# DCDC-12V5V5A.net
KiCad netlist of a schematic drawn in EAGLE
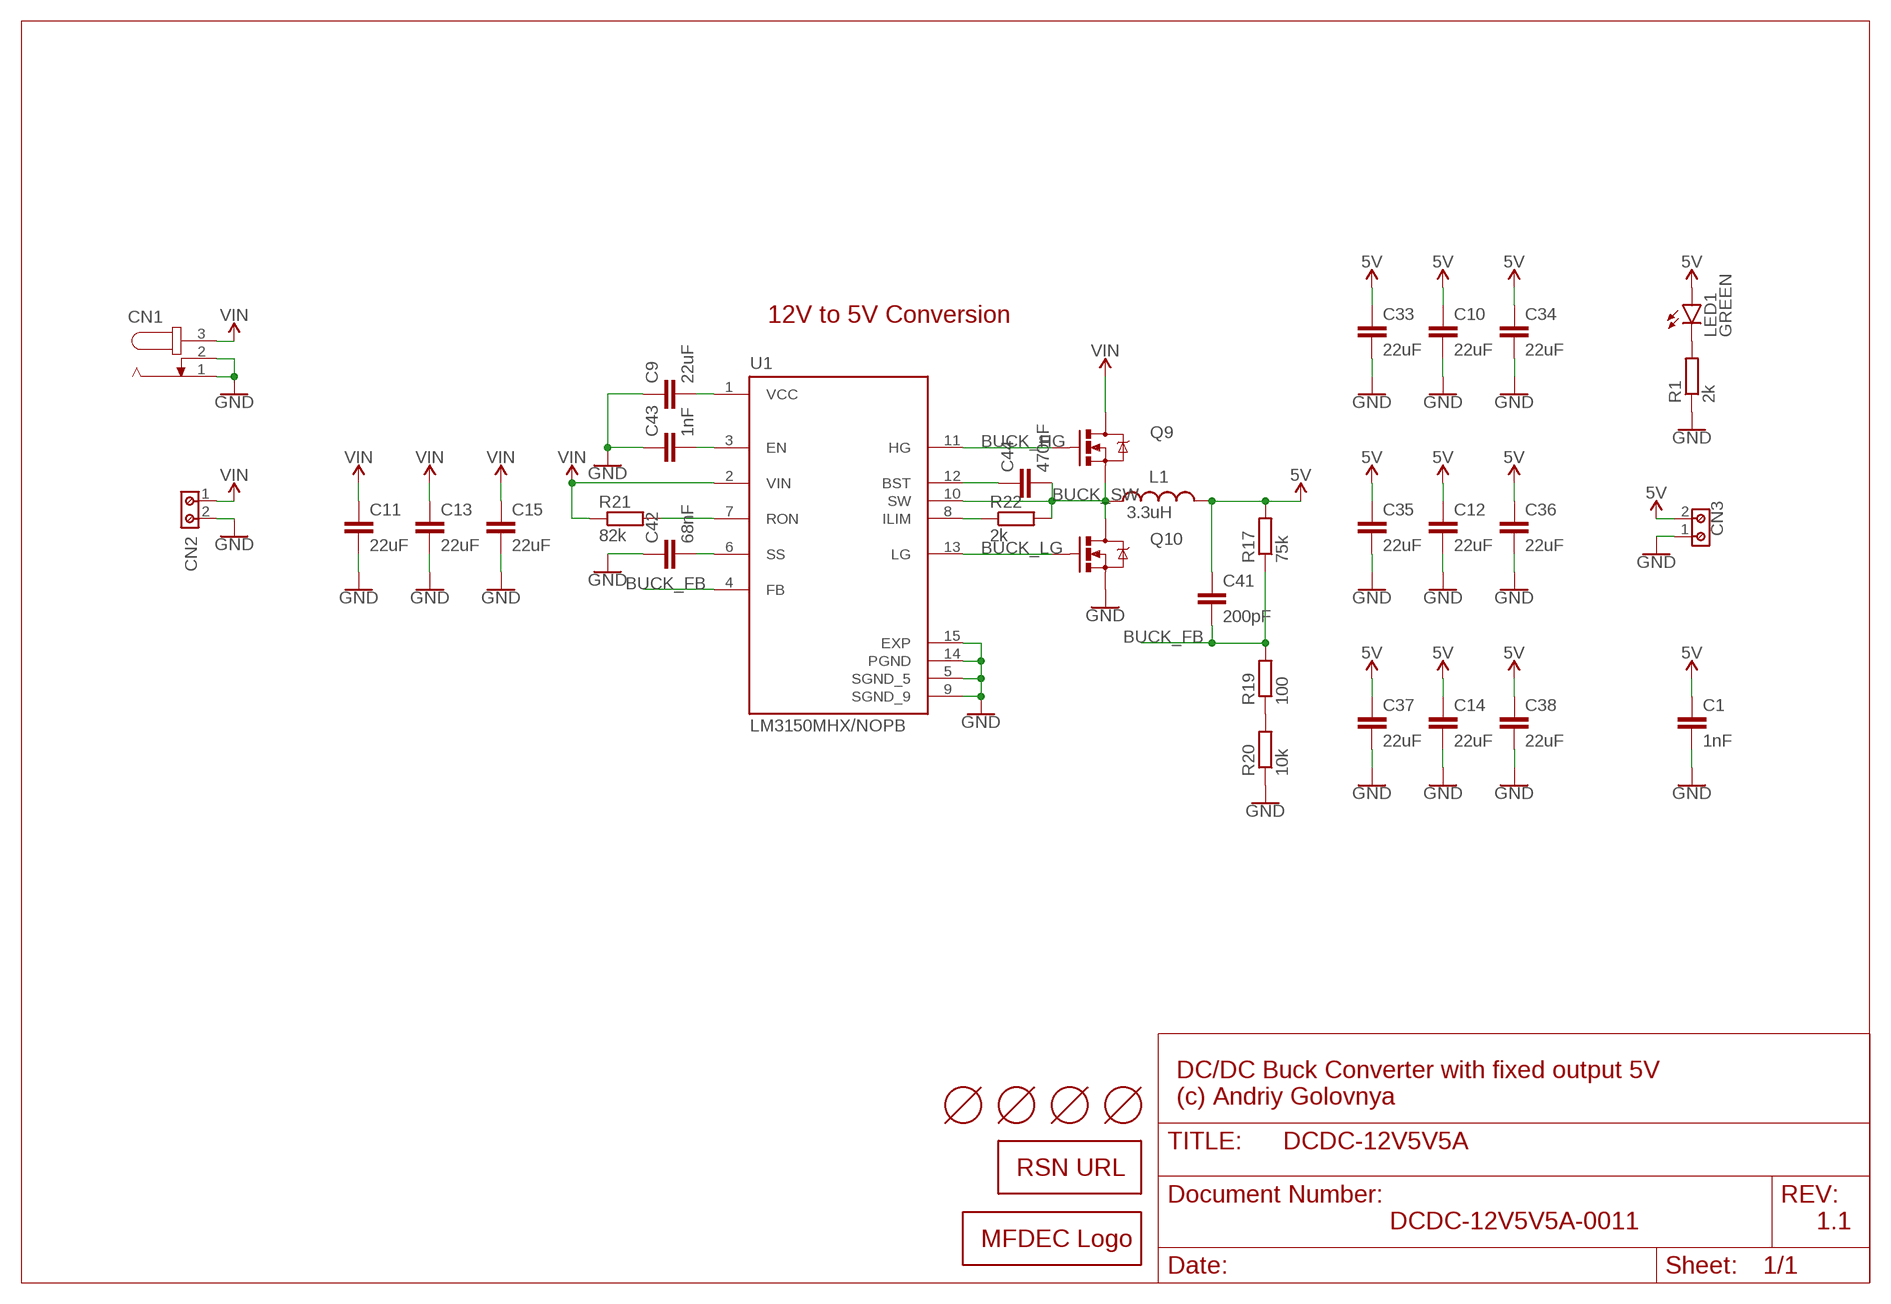
[diagram p0: schematic, sheet 1]

(export (version "E")
  (design (tool "Eeschema 10.0.6"))
  (components
    (comp (ref "C1")
      (value "1nF")
      (footprint "eagle-import:C0603K")
      (libsource (lib "eagle-import") (part "C-EUC0603K"))
    )
    (comp (ref "C9")
      (value "22uF")
      (footprint "eagle-import:C0805K")
      (libsource (lib "eagle-import") (part "C-EUC0805K"))
    )
    (comp (ref "C10")
      (value "22uF")
      (footprint "eagle-import:C0805K")
      (libsource (lib "eagle-import") (part "C-EUC0805K"))
    )
    (comp (ref "C11")
      (value "22uF")
      (footprint "eagle-import:C0805K")
      (libsource (lib "eagle-import") (part "C-EUC0805K"))
    )
    (comp (ref "C12")
      (value "22uF")
      (footprint "eagle-import:C0805K")
      (libsource (lib "eagle-import") (part "C-EUC0805K"))
    )
    (comp (ref "C13")
      (value "22uF")
      (footprint "eagle-import:C0805K")
      (libsource (lib "eagle-import") (part "C-EUC0805K"))
    )
    (comp (ref "C14")
      (value "22uF")
      (footprint "eagle-import:C0805K")
      (libsource (lib "eagle-import") (part "C-EUC0805K"))
    )
    (comp (ref "C15")
      (value "22uF")
      (footprint "eagle-import:C0805K")
      (libsource (lib "eagle-import") (part "C-EUC0805K"))
    )
    (comp (ref "C33")
      (value "22uF")
      (footprint "eagle-import:C0805K")
      (libsource (lib "eagle-import") (part "C-EUC0805K"))
    )
    (comp (ref "C34")
      (value "22uF")
      (footprint "eagle-import:C0805K")
      (libsource (lib "eagle-import") (part "C-EUC0805K"))
    )
    (comp (ref "C35")
      (value "22uF")
      (footprint "eagle-import:C0805K")
      (libsource (lib "eagle-import") (part "C-EUC0805K"))
    )
    (comp (ref "C36")
      (value "22uF")
      (footprint "eagle-import:C0805K")
      (libsource (lib "eagle-import") (part "C-EUC0805K"))
    )
    (comp (ref "C37")
      (value "22uF")
      (footprint "eagle-import:C0805K")
      (libsource (lib "eagle-import") (part "C-EUC0805K"))
    )
    (comp (ref "C38")
      (value "22uF")
      (footprint "eagle-import:C0805K")
      (libsource (lib "eagle-import") (part "C-EUC0805K"))
    )
    (comp (ref "C41")
      (value "200pF")
      (footprint "eagle-import:C0603K")
      (libsource (lib "eagle-import") (part "C-EUC0603K"))
    )
    (comp (ref "C42")
      (value "68nF")
      (footprint "eagle-import:C0603K")
      (libsource (lib "eagle-import") (part "C-EUC0603K"))
    )
    (comp (ref "C43")
      (value "1nF")
      (footprint "eagle-import:C0603K")
      (libsource (lib "eagle-import") (part "C-EUC0603K"))
    )
    (comp (ref "C44")
      (value "470nF")
      (footprint "eagle-import:C0603K")
      (libsource (lib "eagle-import") (part "C-EUC0603K"))
    )
    (comp (ref "CN1")
      (value "JACK-PLUG1")
      (footprint "eagle-import:SPC4078")
      (libsource (lib "eagle-import") (part "JACK-PLUG1"))
    )
    (comp (ref "CN2")
      (value "691213510002")
      (footprint "eagle-import:691213510002")
      (libsource (lib "eagle-import") (part "691213510002"))
    )
    (comp (ref "CN3")
      (value "691213510002")
      (footprint "eagle-import:691213510002")
      (libsource (lib "eagle-import") (part "691213510002"))
    )
    (comp (ref "HOLE1")
      (value "TOOLINGHOLE")
      (footprint "eagle-import:TOOLING-HOLE")
      (libsource (lib "eagle-import") (part "TOOLINGHOLE"))
    )
    (comp (ref "HOLE2")
      (value "TOOLINGHOLE")
      (footprint "eagle-import:TOOLING-HOLE")
      (libsource (lib "eagle-import") (part "TOOLINGHOLE"))
    )
    (comp (ref "HOLE3")
      (value "TOOLINGHOLE")
      (footprint "eagle-import:TOOLING-HOLE")
      (libsource (lib "eagle-import") (part "TOOLINGHOLE"))
    )
    (comp (ref "HOLE4")
      (value "TOOLINGHOLE")
      (footprint "eagle-import:TOOLING-HOLE")
      (libsource (lib "eagle-import") (part "TOOLINGHOLE"))
    )
    (comp (ref "L1")
      (value "3.3uH")
      (footprint "eagle-import:WE-CHSA_1011")
      (libsource (lib "eagle-import") (part "WE-CHSA_1011_7843330330"))
    )
    (comp (ref "LED1")
      (value "GREEN")
      (footprint "eagle-import:SML0603")
      (libsource (lib "eagle-import") (part "LEDSML0603"))
    )
    (comp (ref "LOGO1")
      (value "RSNURL_QR_8MM")
      (footprint "eagle-import:RSNURL_QR_8MM")
      (libsource (lib "eagle-import") (part "RSNURL_QR_8MM"))
    )
    (comp (ref "LOGO2")
      (value "MFDECLOGO_L_10MM")
      (footprint "eagle-import:MFDEC_L_10MM")
      (libsource (lib "eagle-import") (part "MFDECLOGO_L_10MM"))
    )
    (comp (ref "Q9")
      (value "NMOSFET")
      (footprint "eagle-import:DPAK")
      (libsource (lib "eagle-import") (part "MOSFET-NCHANNELFDD8780"))
    )
    (comp (ref "Q10")
      (value "NMOSFET")
      (footprint "eagle-import:DPAK")
      (libsource (lib "eagle-import") (part "MOSFET-NCHANNELFDD8780"))
    )
    (comp (ref "R1")
      (value "2k")
      (footprint "eagle-import:R0603")
      (libsource (lib "eagle-import") (part "R-EU_R0603"))
    )
    (comp (ref "R17")
      (value "75k")
      (footprint "eagle-import:R0603")
      (libsource (lib "eagle-import") (part "R-EU_R0603"))
    )
    (comp (ref "R19")
      (value "100")
      (footprint "eagle-import:R0603")
      (libsource (lib "eagle-import") (part "R-EU_R0603"))
    )
    (comp (ref "R20")
      (value "10k")
      (footprint "eagle-import:R0603")
      (libsource (lib "eagle-import") (part "R-EU_R0603"))
    )
    (comp (ref "R21")
      (value "82k")
      (footprint "eagle-import:R0603")
      (libsource (lib "eagle-import") (part "R-EU_R0603"))
    )
    (comp (ref "R22")
      (value "2k")
      (footprint "eagle-import:R0603")
      (libsource (lib "eagle-import") (part "R-EU_R0603"))
    )
    (comp (ref "U1")
      (value "LM3150MHX/NOPB")
      (footprint "eagle-import:SOP65P640X110-15N")
      (fields (field (name "MF") "Texas Instruments"))
      (libsource (lib "eagle-import") (part "LM3150MHX/NOPB"))
    )
  )
  (nets
    (net (code "1") (name "/BUCK_FB") (class "Default")
      (node (ref "C41") (pin "2") (pinfunction "2_2") (pintype "passive"))
      (node (ref "R17") (pin "1") (pinfunction "1_1") (pintype "passive"))
      (node (ref "R19") (pin "2") (pinfunction "2_2") (pintype "passive"))
      (node (ref "U1") (pin "4") (pinfunction "FB_4") (pintype "input"))
    )
    (net (code "2") (name "/BUCK_HG") (class "Default")
      (node (ref "Q9") (pin "1") (pinfunction "G_1") (pintype "passive"))
      (node (ref "U1") (pin "11") (pinfunction "HG_11") (pintype "output"))
    )
    (net (code "3") (name "/BUCK_LG") (class "Default")
      (node (ref "Q10") (pin "1") (pinfunction "G_1") (pintype "passive"))
      (node (ref "U1") (pin "13") (pinfunction "LG_13") (pintype "output"))
    )
    (net (code "4") (name "/BUCK_SW") (class "Default")
      (node (ref "C44") (pin "2") (pinfunction "2_2") (pintype "passive"))
      (node (ref "L1") (pin "1") (pinfunction "1_1") (pintype "passive"))
      (node (ref "Q10") (pin "4") (pinfunction "D_4") (pintype "passive"))
      (node (ref "Q9") (pin "3") (pinfunction "S_3") (pintype "passive"))
      (node (ref "R22") (pin "2") (pinfunction "2_2") (pintype "passive"))
      (node (ref "U1") (pin "10") (pinfunction "SW_10") (pintype "output"))
    )
    (net (code "5") (name "5V") (class "Default")
      (node (ref "C1") (pin "1") (pinfunction "1_1") (pintype "passive"))
      (node (ref "C10") (pin "1") (pinfunction "1_1") (pintype "passive"))
      (node (ref "C12") (pin "1") (pinfunction "1_1") (pintype "passive"))
      (node (ref "C14") (pin "1") (pinfunction "1_1") (pintype "passive"))
      (node (ref "C33") (pin "1") (pinfunction "1_1") (pintype "passive"))
      (node (ref "C34") (pin "1") (pinfunction "1_1") (pintype "passive"))
      (node (ref "C35") (pin "1") (pinfunction "1_1") (pintype "passive"))
      (node (ref "C36") (pin "1") (pinfunction "1_1") (pintype "passive"))
      (node (ref "C37") (pin "1") (pinfunction "1_1") (pintype "passive"))
      (node (ref "C38") (pin "1") (pinfunction "1_1") (pintype "passive"))
      (node (ref "C41") (pin "1") (pinfunction "1_1") (pintype "passive"))
      (node (ref "CN3") (pin "2") (pinfunction "2_2") (pintype "passive"))
      (node (ref "L1") (pin "2") (pinfunction "2_2") (pintype "passive"))
      (node (ref "LED1") (pin "A") (pinfunction "A_A") (pintype "passive"))
      (node (ref "R17") (pin "2") (pinfunction "2_2") (pintype "passive"))
    )
    (net (code "6") (name "GND") (class "Default")
      (node (ref "C1") (pin "2") (pinfunction "2_2") (pintype "passive"))
      (node (ref "C10") (pin "2") (pinfunction "2_2") (pintype "passive"))
      (node (ref "C11") (pin "2") (pinfunction "2_2") (pintype "passive"))
      (node (ref "C12") (pin "2") (pinfunction "2_2") (pintype "passive"))
      (node (ref "C13") (pin "2") (pinfunction "2_2") (pintype "passive"))
      (node (ref "C14") (pin "2") (pinfunction "2_2") (pintype "passive"))
      (node (ref "C15") (pin "2") (pinfunction "2_2") (pintype "passive"))
      (node (ref "C33") (pin "2") (pinfunction "2_2") (pintype "passive"))
      (node (ref "C34") (pin "2") (pinfunction "2_2") (pintype "passive"))
      (node (ref "C35") (pin "2") (pinfunction "2_2") (pintype "passive"))
      (node (ref "C36") (pin "2") (pinfunction "2_2") (pintype "passive"))
      (node (ref "C37") (pin "2") (pinfunction "2_2") (pintype "passive"))
      (node (ref "C38") (pin "2") (pinfunction "2_2") (pintype "passive"))
      (node (ref "C42") (pin "1") (pinfunction "1_1") (pintype "passive"))
      (node (ref "C43") (pin "1") (pinfunction "1_1") (pintype "passive"))
      (node (ref "C9") (pin "1") (pinfunction "1_1") (pintype "passive"))
      (node (ref "CN1") (pin "1") (pinfunction "1_1") (pintype "passive"))
      (node (ref "CN1") (pin "2") (pinfunction "2_2") (pintype "passive"))
      (node (ref "CN2") (pin "2") (pinfunction "2_2") (pintype "passive"))
      (node (ref "CN3") (pin "1") (pinfunction "1_1") (pintype "passive"))
      (node (ref "Q10") (pin "3") (pinfunction "S_3") (pintype "passive"))
      (node (ref "R1") (pin "1") (pinfunction "1_1") (pintype "passive"))
      (node (ref "R20") (pin "1") (pinfunction "1_1") (pintype "passive"))
      (node (ref "U1") (pin "14") (pinfunction "PGND_14") (pintype "power_in"))
      (node (ref "U1") (pin "15") (pinfunction "EXP_15") (pintype "power_in"))
      (node (ref "U1") (pin "5") (pinfunction "SGND_5_5") (pintype "power_in"))
      (node (ref "U1") (pin "9") (pinfunction "SGND_9_9") (pintype "power_in"))
    )
    (net (code "7") (name "Net-(LED1-PadC)") (class "Default")
      (node (ref "LED1") (pin "C") (pinfunction "C_C") (pintype "passive"))
      (node (ref "R1") (pin "2") (pinfunction "2_2") (pintype "passive"))
    )
    (net (code "8") (name "Net-(R19-Pad1)") (class "Default")
      (node (ref "R19") (pin "1") (pinfunction "1_1") (pintype "passive"))
      (node (ref "R20") (pin "2") (pinfunction "2_2") (pintype "passive"))
    )
    (net (code "9") (name "Net-(U1-BST)") (class "Default")
      (node (ref "C44") (pin "1") (pinfunction "1_1") (pintype "passive"))
      (node (ref "U1") (pin "12") (pinfunction "BST_12") (pintype "passive"))
    )
    (net (code "10") (name "Net-(U1-EN)") (class "Default")
      (node (ref "C43") (pin "2") (pinfunction "2_2") (pintype "passive"))
      (node (ref "U1") (pin "3") (pinfunction "EN_3") (pintype "input"))
    )
    (net (code "11") (name "Net-(U1-ILIM)") (class "Default")
      (node (ref "R22") (pin "1") (pinfunction "1_1") (pintype "passive"))
      (node (ref "U1") (pin "8") (pinfunction "ILIM_8") (pintype "passive"))
    )
    (net (code "12") (name "Net-(U1-RON)") (class "Default")
      (node (ref "R21") (pin "2") (pinfunction "2_2") (pintype "passive"))
      (node (ref "U1") (pin "7") (pinfunction "RON_7") (pintype "input"))
    )
    (net (code "13") (name "Net-(U1-SS)") (class "Default")
      (node (ref "C42") (pin "2") (pinfunction "2_2") (pintype "passive"))
      (node (ref "U1") (pin "6") (pinfunction "SS_6") (pintype "input"))
    )
    (net (code "14") (name "Net-(U1-VCC)") (class "Default")
      (node (ref "C9") (pin "2") (pinfunction "2_2") (pintype "passive"))
      (node (ref "U1") (pin "1") (pinfunction "VCC_1") (pintype "power_in"))
    )
    (net (code "15") (name "VIN") (class "Default")
      (node (ref "C11") (pin "1") (pinfunction "1_1") (pintype "passive"))
      (node (ref "C13") (pin "1") (pinfunction "1_1") (pintype "passive"))
      (node (ref "C15") (pin "1") (pinfunction "1_1") (pintype "passive"))
      (node (ref "CN1") (pin "3") (pinfunction "3_3") (pintype "passive"))
      (node (ref "CN2") (pin "1") (pinfunction "1_1") (pintype "passive"))
      (node (ref "Q9") (pin "4") (pinfunction "D_4") (pintype "passive"))
      (node (ref "R21") (pin "1") (pinfunction "1_1") (pintype "passive"))
      (node (ref "U1") (pin "2") (pinfunction "VIN_2") (pintype "input"))
    )
  )
)
